# space_invaders_v21.net
KiCad netlist of a schematic drawn in EAGLE
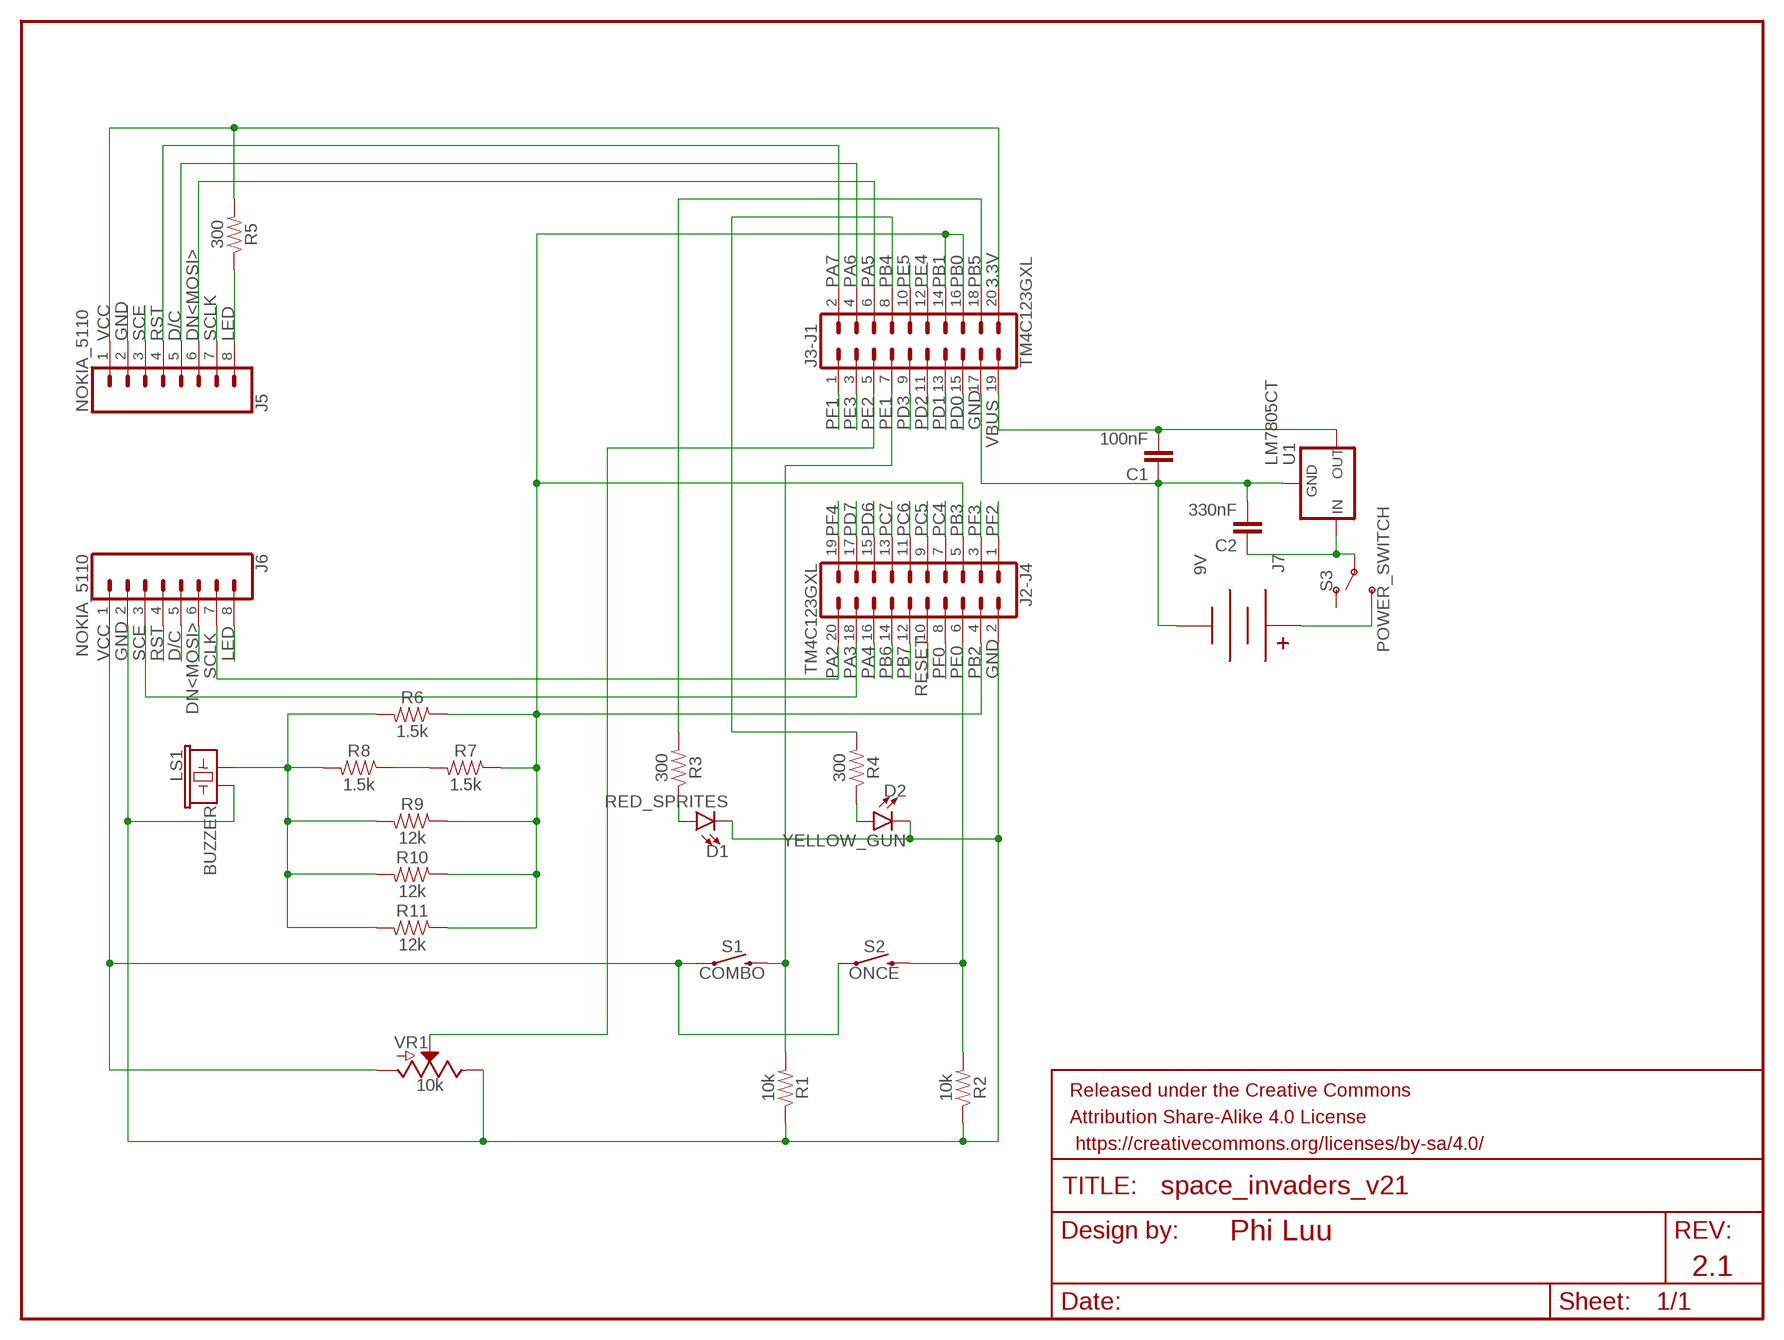
[diagram p0: schematic, sheet 1]

(export (version "E")
  (design (tool "Eeschema 10.0.6"))
  (components
    (comp (ref "C1")
      (value "100nF")
      (footprint "eagle-import:CAP-PTH-SMALL-KIT")
      (libsource (lib "eagle-import") (part "0.1UF-KIT-EZ-50V-20%"))
    )
    (comp (ref "C2")
      (value "330nF")
      (footprint "eagle-import:CAP-PTH-SMALL-KIT")
      (libsource (lib "eagle-import") (part "0.1UF-KIT-EZ-50V-20%"))
    )
    (comp (ref "D1")
      (value "RED_SPRITES")
      (footprint "eagle-import:LED_5MM")
      (libsource (lib "eagle-import") (part "LED5MM"))
    )
    (comp (ref "D2")
      (value "YELLOW_GUN")
      (footprint "eagle-import:LED_5MM")
      (libsource (lib "eagle-import") (part "LED5MM"))
    )
    (comp (ref "FRAME1")
      (value "FRAME-LETTER")
      (footprint "eagle-import:CREATIVE_COMMONS")
      (libsource (lib "eagle-import") (part "FRAME-LETTER"))
    )
    (comp (ref "J2-J4")
      (value "TM4C123GXL")
      (footprint "eagle-import:2X10")
      (libsource (lib "eagle-import") (part "CONN_10X2"))
    )
    (comp (ref "J3-J1")
      (value "TM4C123GXL")
      (footprint "eagle-import:2X10")
      (libsource (lib "eagle-import") (part "CONN_10X2"))
    )
    (comp (ref "J5")
      (value "NOKIA_5110")
      (footprint "eagle-import:1X08")
      (libsource (lib "eagle-import") (part "CONN_08{dblquote}"))
    )
    (comp (ref "J6")
      (value "NOKIA_5110")
      (footprint "eagle-import:1X08")
      (libsource (lib "eagle-import") (part "CONN_08{dblquote}"))
    )
    (comp (ref "J7")
      (value "9V")
      (footprint "eagle-import:BC9VPC")
      (libsource (lib "eagle-import") (part "BC9VPC"))
    )
    (comp (ref "LS1")
      (value "BUZZER")
      (footprint "eagle-import:BUZZER-12MM")
      (libsource (lib "eagle-import") (part "BUZZER-PTH"))
    )
    (comp (ref "R1")
      (value "10k")
      (footprint "eagle-import:AXIAL-0.3")
      (libsource (lib "eagle-import") (part "10KOHM-HORIZ-1/4W-5%"))
    )
    (comp (ref "R2")
      (value "10k")
      (footprint "eagle-import:AXIAL-0.3")
      (libsource (lib "eagle-import") (part "10KOHM-HORIZ-1/4W-5%"))
    )
    (comp (ref "R3")
      (value "300")
      (footprint "eagle-import:AXIAL-0.3")
      (libsource (lib "eagle-import") (part "1KOHM-HORIZ-1/4W-5%"))
    )
    (comp (ref "R4")
      (value "300")
      (footprint "eagle-import:AXIAL-0.3")
      (libsource (lib "eagle-import") (part "1KOHM-HORIZ-1/4W-5%"))
    )
    (comp (ref "R5")
      (value "300")
      (footprint "eagle-import:AXIAL-0.3")
      (libsource (lib "eagle-import") (part "1KOHM-HORIZ-1/4W-5%"))
    )
    (comp (ref "R6")
      (value "1.5k")
      (footprint "eagle-import:AXIAL-0.3")
      (libsource (lib "eagle-import") (part "1KOHM-HORIZ-1/4W-5%"))
    )
    (comp (ref "R7")
      (value "1.5k")
      (footprint "eagle-import:AXIAL-0.3")
      (libsource (lib "eagle-import") (part "1KOHM-HORIZ-1/4W-5%"))
    )
    (comp (ref "R8")
      (value "1.5k")
      (footprint "eagle-import:AXIAL-0.3")
      (libsource (lib "eagle-import") (part "1KOHM-HORIZ-1/4W-5%"))
    )
    (comp (ref "R9")
      (value "12k")
      (footprint "eagle-import:AXIAL-0.3")
      (libsource (lib "eagle-import") (part "1KOHM-HORIZ-1/4W-5%"))
    )
    (comp (ref "R10")
      (value "12k")
      (footprint "eagle-import:AXIAL-0.3")
      (libsource (lib "eagle-import") (part "1KOHM-HORIZ-1/4W-5%"))
    )
    (comp (ref "R11")
      (value "12k")
      (footprint "eagle-import:AXIAL-0.3")
      (libsource (lib "eagle-import") (part "1KOHM-HORIZ-1/4W-5%"))
    )
    (comp (ref "S1")
      (value "COMBO")
      (footprint "eagle-import:TACTILE_SWITCH_PTH_6.0MM")
      (libsource (lib "eagle-import") (part "MOMENTARY-SWITCH-SPST-PTH-6.0MM"))
    )
    (comp (ref "S2")
      (value "ONCE")
      (footprint "eagle-import:TACTILE_SWITCH_PTH_6.0MM")
      (libsource (lib "eagle-import") (part "MOMENTARY-SWITCH-SPST-PTH-6.0MM"))
    )
    (comp (ref "S3")
      (value "POWER_SWITCH")
      (footprint "eagle-import:SWITCH_SPDT_PTH_11.6X4.0MM")
      (libsource (lib "eagle-import") (part "SWITCH-SPDT-PTH-11.6X4.0MM"))
    )
    (comp (ref "U1")
      (value "LM7805CT")
      (footprint "eagle-import:TO220-IGO")
      (libsource (lib "eagle-import") (part "V_REG_78XXSINK"))
    )
    (comp (ref "VR1")
      (value "10k")
      (footprint "eagle-import:SLIDER-MEDIUM")
      (libsource (lib "eagle-import") (part "POTENTIOMETER_SLIDE-30MM-1/10W-20%"))
    )
  )
  (nets
    (net (code "1") (name "/3.3V") (class "Default")
      (node (ref "J3-J1") (pin "20") (pinfunction "20_20") (pintype "passive"))
      (node (ref "J5") (pin "1") (pinfunction "1_1") (pintype "passive"))
      (node (ref "J6") (pin "1") (pinfunction "1_1") (pintype "passive"))
      (node (ref "R5") (pin "P$2") (pinfunction "2_P$2") (pintype "passive"))
      (node (ref "S1") (pin "1") (pinfunction "1_1") (pintype "passive"))
      (node (ref "S2") (pin "1") (pinfunction "1_1") (pintype "passive"))
      (node (ref "VR1") (pin "BOTTOM") (pinfunction "A_BOTTOM") (pintype "passive"))
    )
    (net (code "2") (name "/GND") (class "Default")
      (node (ref "C1") (pin "1") (pinfunction "1_1") (pintype "passive"))
      (node (ref "C2") (pin "2") (pinfunction "2_2") (pintype "passive"))
      (node (ref "D1") (pin "K") (pinfunction "C_K") (pintype "passive"))
      (node (ref "D2") (pin "K") (pinfunction "C_K") (pintype "passive"))
      (node (ref "J2-J4") (pin "2") (pinfunction "2_2") (pintype "passive"))
      (node (ref "J3-J1") (pin "17") (pinfunction "17_17") (pintype "passive"))
      (node (ref "J5") (pin "2") (pinfunction "2_2") (pintype "passive"))
      (node (ref "J6") (pin "2") (pinfunction "2_2") (pintype "passive"))
      (node (ref "J7") (pin "V-") (pinfunction "V-_V-") (pintype "bidirectional"))
      (node (ref "LS1") (pin "-") (pinfunction "2_-") (pintype "passive"))
      (node (ref "R1") (pin "P$1") (pinfunction "1_P$1") (pintype "passive"))
      (node (ref "R2") (pin "P$1") (pinfunction "1_P$1") (pintype "passive"))
      (node (ref "U1") (pin "GND") (pinfunction "GND_GND") (pintype "input"))
      (node (ref "VR1") (pin "TOP") (pinfunction "E_TOP") (pintype "passive"))
    )
    (net (code "3") (name "/LED") (class "Default")
      (node (ref "J5") (pin "8") (pinfunction "8_8") (pintype "passive"))
      (node (ref "J6") (pin "8") (pinfunction "8_8") (pintype "passive"))
      (node (ref "R5") (pin "P$1") (pinfunction "1_P$1") (pintype "passive"))
    )
    (net (code "4") (name "/PA2") (class "Default")
      (node (ref "J2-J4") (pin "20") (pinfunction "20_20") (pintype "passive"))
      (node (ref "J5") (pin "7") (pinfunction "7_7") (pintype "passive"))
      (node (ref "J6") (pin "7") (pinfunction "7_7") (pintype "passive"))
    )
    (net (code "5") (name "/PA3") (class "Default")
      (node (ref "J2-J4") (pin "18") (pinfunction "18_18") (pintype "passive"))
      (node (ref "J5") (pin "3") (pinfunction "3_3") (pintype "passive"))
      (node (ref "J6") (pin "3") (pinfunction "3_3") (pintype "passive"))
    )
    (net (code "6") (name "/PA4") (class "Default")
      (node (ref "J2-J4") (pin "16") (pinfunction "16_16") (pintype "passive"))
    )
    (net (code "7") (name "/PA5") (class "Default")
      (node (ref "J3-J1") (pin "6") (pinfunction "6_6") (pintype "passive"))
      (node (ref "J5") (pin "6") (pinfunction "6_6") (pintype "passive"))
      (node (ref "J6") (pin "6") (pinfunction "6_6") (pintype "passive"))
    )
    (net (code "8") (name "/PA6") (class "Default")
      (node (ref "J3-J1") (pin "4") (pinfunction "4_4") (pintype "passive"))
      (node (ref "J5") (pin "5") (pinfunction "5_5") (pintype "passive"))
      (node (ref "J6") (pin "5") (pinfunction "5_5") (pintype "passive"))
    )
    (net (code "9") (name "/PA7") (class "Default")
      (node (ref "J3-J1") (pin "2") (pinfunction "2_2") (pintype "passive"))
      (node (ref "J5") (pin "4") (pinfunction "4_4") (pintype "passive"))
      (node (ref "J6") (pin "4") (pinfunction "4_4") (pintype "passive"))
    )
    (net (code "10") (name "/PB4") (class "Default")
      (node (ref "J3-J1") (pin "8") (pinfunction "8_8") (pintype "passive"))
      (node (ref "R4") (pin "P$2") (pinfunction "2_P$2") (pintype "passive"))
    )
    (net (code "11") (name "/PB5") (class "Default")
      (node (ref "J3-J1") (pin "18") (pinfunction "18_18") (pintype "passive"))
      (node (ref "R3") (pin "P$2") (pinfunction "2_P$2") (pintype "passive"))
    )
    (net (code "12") (name "/PB6") (class "Default")
      (node (ref "J2-J4") (pin "14") (pinfunction "14_14") (pintype "passive"))
    )
    (net (code "13") (name "/PB7") (class "Default")
      (node (ref "J2-J4") (pin "12") (pinfunction "12_12") (pintype "passive"))
    )
    (net (code "14") (name "/PC4") (class "Default")
      (node (ref "J2-J4") (pin "7") (pinfunction "7_7") (pintype "passive"))
    )
    (net (code "15") (name "/PC5") (class "Default")
      (node (ref "J2-J4") (pin "9") (pinfunction "9_9") (pintype "passive"))
    )
    (net (code "16") (name "/PC6") (class "Default")
      (node (ref "J2-J4") (pin "11") (pinfunction "11_11") (pintype "passive"))
    )
    (net (code "17") (name "/PC7") (class "Default")
      (node (ref "J2-J4") (pin "13") (pinfunction "13_13") (pintype "passive"))
    )
    (net (code "18") (name "/PD0") (class "Default")
      (node (ref "J3-J1") (pin "15") (pinfunction "15_15") (pintype "passive"))
    )
    (net (code "19") (name "/PD1") (class "Default")
      (node (ref "J3-J1") (pin "13") (pinfunction "13_13") (pintype "passive"))
    )
    (net (code "20") (name "/PD2") (class "Default")
      (node (ref "J3-J1") (pin "11") (pinfunction "11_11") (pintype "passive"))
    )
    (net (code "21") (name "/PD3") (class "Default")
      (node (ref "J3-J1") (pin "9") (pinfunction "9_9") (pintype "passive"))
    )
    (net (code "22") (name "/PD6") (class "Default")
      (node (ref "J2-J4") (pin "15") (pinfunction "15_15") (pintype "passive"))
    )
    (net (code "23") (name "/PD7") (class "Default")
      (node (ref "J2-J4") (pin "17") (pinfunction "17_17") (pintype "passive"))
    )
    (net (code "24") (name "/PE0") (class "Default")
      (node (ref "J2-J4") (pin "6") (pinfunction "6_6") (pintype "passive"))
      (node (ref "R2") (pin "P$2") (pinfunction "2_P$2") (pintype "passive"))
      (node (ref "S2") (pin "3") (pinfunction "2_3") (pintype "passive"))
    )
    (net (code "25") (name "/PE1") (class "Default")
      (node (ref "J3-J1") (pin "7") (pinfunction "7_7") (pintype "passive"))
      (node (ref "R1") (pin "P$2") (pinfunction "2_P$2") (pintype "passive"))
      (node (ref "S1") (pin "3") (pinfunction "2_3") (pintype "passive"))
    )
    (net (code "26") (name "/PE2") (class "Default")
      (node (ref "J3-J1") (pin "5") (pinfunction "5_5") (pintype "passive"))
      (node (ref "VR1") (pin "WIPER") (pinfunction "S_WIPER") (pintype "passive"))
    )
    (net (code "27") (name "/PE3") (class "Default")
      (node (ref "J3-J1") (pin "3") (pinfunction "3_3") (pintype "passive"))
    )
    (net (code "28") (name "/PE4") (class "Default")
      (node (ref "J3-J1") (pin "12") (pinfunction "12_12") (pintype "passive"))
    )
    (net (code "29") (name "/PE5") (class "Default")
      (node (ref "J3-J1") (pin "10") (pinfunction "10_10") (pintype "passive"))
    )
    (net (code "30") (name "/PF0") (class "Default")
      (node (ref "J2-J4") (pin "8") (pinfunction "8_8") (pintype "passive"))
    )
    (net (code "31") (name "/PF1") (class "Default")
      (node (ref "J3-J1") (pin "1") (pinfunction "1_1") (pintype "passive"))
    )
    (net (code "32") (name "/PF2") (class "Default")
      (node (ref "J2-J4") (pin "1") (pinfunction "1_1") (pintype "passive"))
    )
    (net (code "33") (name "/PF3") (class "Default")
      (node (ref "J2-J4") (pin "3") (pinfunction "3_3") (pintype "passive"))
    )
    (net (code "34") (name "/PF4") (class "Default")
      (node (ref "J2-J4") (pin "19") (pinfunction "19_19") (pintype "passive"))
    )
    (net (code "35") (name "/RESET") (class "Default")
      (node (ref "J2-J4") (pin "10") (pinfunction "10_10") (pintype "passive"))
    )
    (net (code "36") (name "/VBUS") (class "Default")
      (node (ref "C1") (pin "2") (pinfunction "2_2") (pintype "passive"))
      (node (ref "J3-J1") (pin "19") (pinfunction "19_19") (pintype "passive"))
      (node (ref "U1") (pin "OUT") (pinfunction "OUT_OUT") (pintype "passive"))
    )
    (net (code "37") (name "Net-(LS1-1)") (class "Default")
      (node (ref "LS1") (pin "+") (pinfunction "1_+") (pintype "passive"))
      (node (ref "R10") (pin "P$2") (pinfunction "2_P$2") (pintype "passive"))
      (node (ref "R11") (pin "P$2") (pinfunction "2_P$2") (pintype "passive"))
      (node (ref "R6") (pin "P$2") (pinfunction "2_P$2") (pintype "passive"))
      (node (ref "R8") (pin "P$2") (pinfunction "2_P$2") (pintype "passive"))
      (node (ref "R9") (pin "P$2") (pinfunction "2_P$2") (pintype "passive"))
    )
    (net (code "38") (name "Net-(R3-1)") (class "Default")
      (node (ref "D1") (pin "A") (pinfunction "A_A") (pintype "passive"))
      (node (ref "R3") (pin "P$1") (pinfunction "1_P$1") (pintype "passive"))
    )
    (net (code "39") (name "Net-(R4-1)") (class "Default")
      (node (ref "D2") (pin "A") (pinfunction "A_A") (pintype "passive"))
      (node (ref "R4") (pin "P$1") (pinfunction "1_P$1") (pintype "passive"))
    )
    (net (code "40") (name "Net-(R7-2)") (class "Default")
      (node (ref "R7") (pin "P$2") (pinfunction "2_P$2") (pintype "passive"))
      (node (ref "R8") (pin "P$1") (pinfunction "1_P$1") (pintype "passive"))
    )
    (net (code "41") (name "Net-(R10-1)") (class "Default")
      (node (ref "J2-J4") (pin "4") (pinfunction "4_4") (pintype "passive"))
      (node (ref "J2-J4") (pin "5") (pinfunction "5_5") (pintype "passive"))
      (node (ref "J3-J1") (pin "14") (pinfunction "14_14") (pintype "passive"))
      (node (ref "J3-J1") (pin "16") (pinfunction "16_16") (pintype "passive"))
      (node (ref "R10") (pin "P$1") (pinfunction "1_P$1") (pintype "passive"))
      (node (ref "R11") (pin "P$1") (pinfunction "1_P$1") (pintype "passive"))
      (node (ref "R6") (pin "P$1") (pinfunction "1_P$1") (pintype "passive"))
      (node (ref "R7") (pin "P$1") (pinfunction "1_P$1") (pintype "passive"))
      (node (ref "R9") (pin "P$1") (pinfunction "1_P$1") (pintype "passive"))
    )
    (net (code "42") (name "Net-(S3-P)") (class "Default")
      (node (ref "C2") (pin "1") (pinfunction "1_1") (pintype "passive"))
      (node (ref "S3") (pin "2") (pinfunction "P_2") (pintype "passive"))
      (node (ref "U1") (pin "IN") (pinfunction "IN_IN") (pintype "input"))
    )
    (net (code "43") (name "Net-(S3-S)") (class "Default")
      (node (ref "J7") (pin "V+") (pinfunction "V+_V+") (pintype "bidirectional"))
      (node (ref "S3") (pin "3") (pinfunction "S_3") (pintype "passive"))
    )
    (net (code "44") (name "unconnected-(S3-O-Pad1)") (class "Default")
      (node (ref "S3") (pin "1") (pinfunction "O_1") (pintype "passive"))
    )
  )
)
